# RFID_System_Board.net
KiCad netlist of a schematic drawn in EAGLE
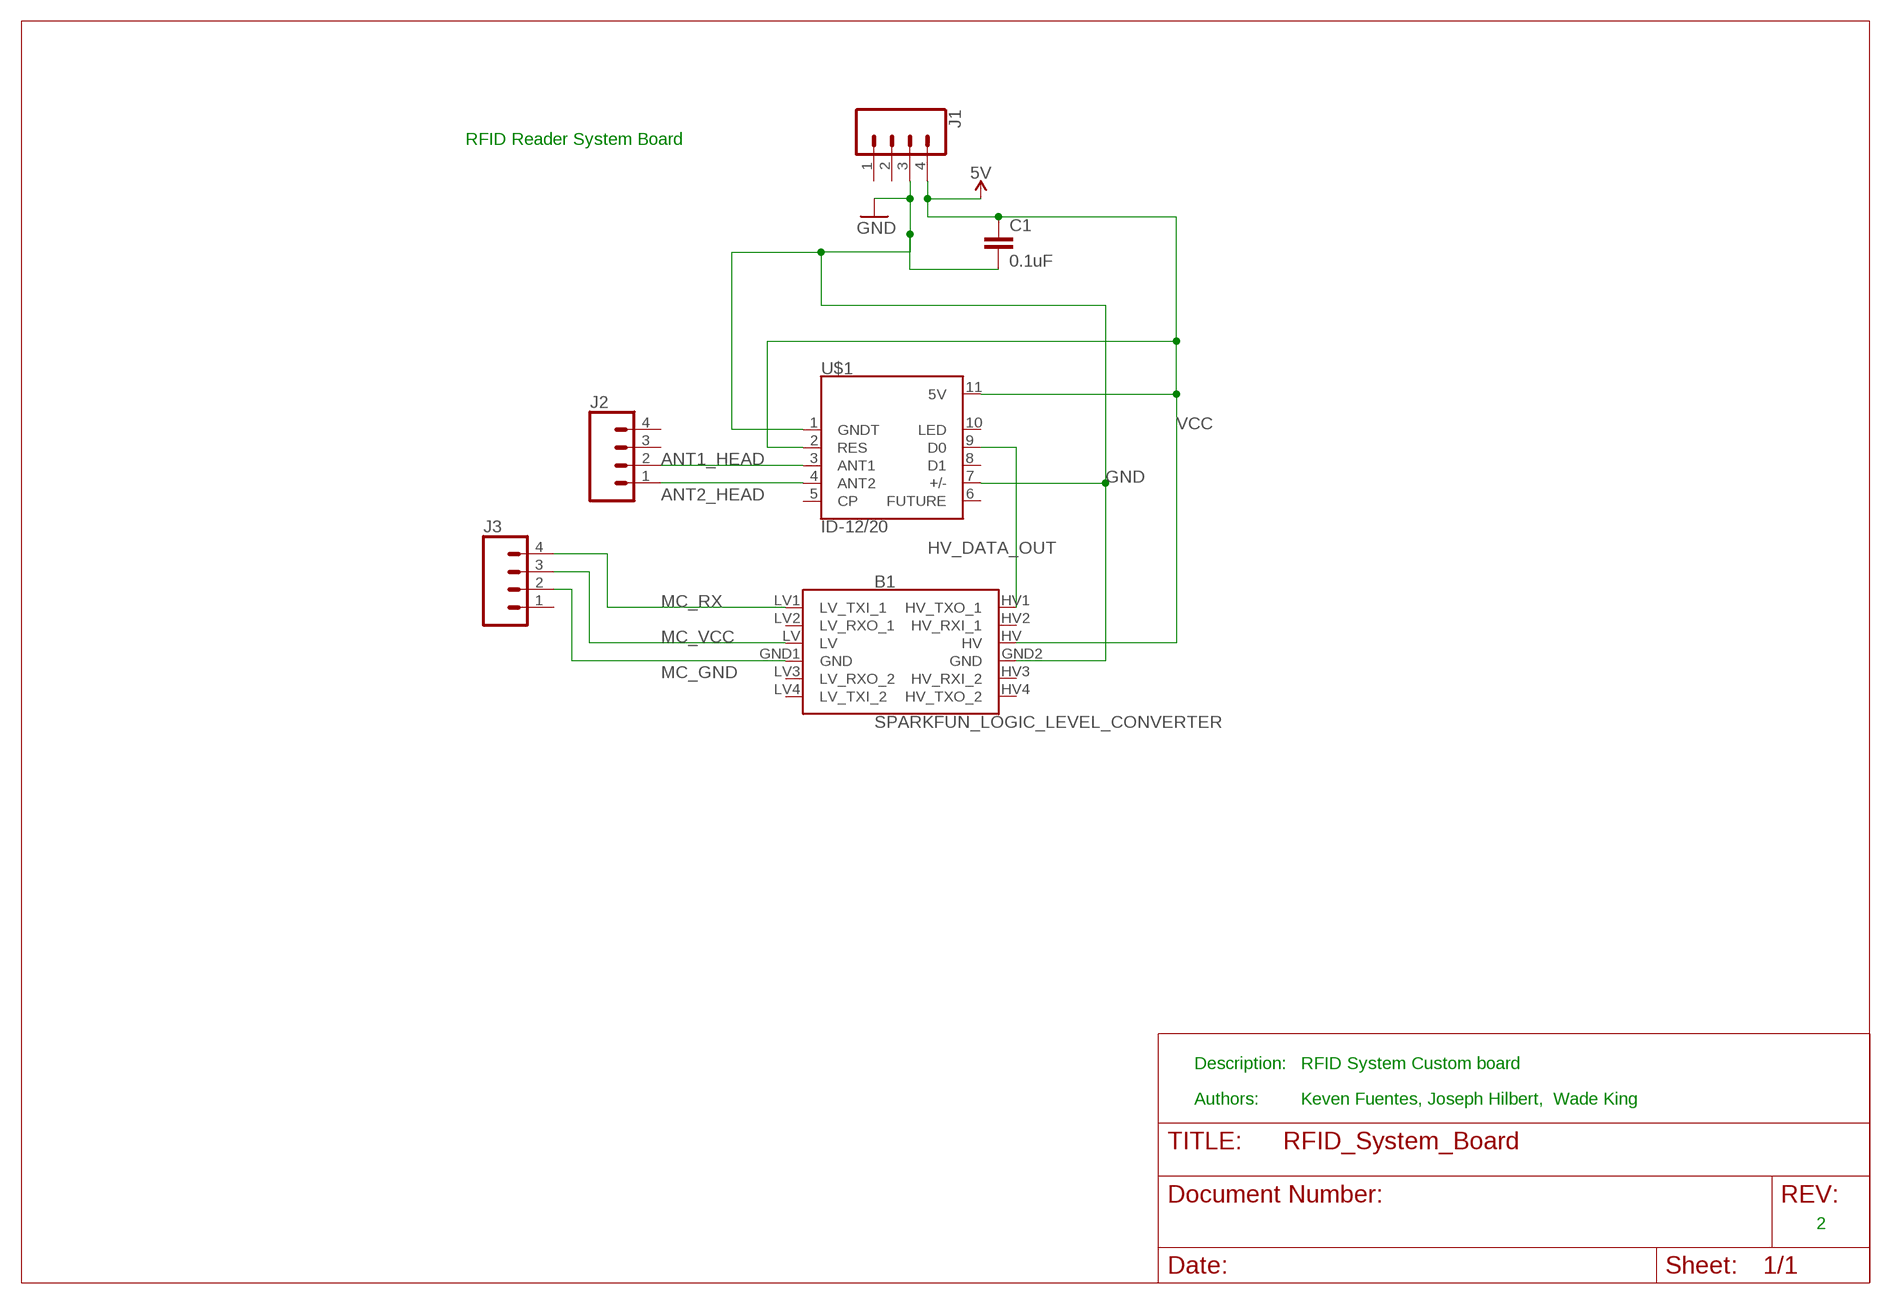
[diagram p0: schematic, sheet 1]

(export (version "E")
  (design (tool "Eeschema 10.0.6"))
  (components
    (comp (ref "B1")
      (value "SPARKFUN_LOGIC_LEVEL_CONVERTER")
      (footprint "eagle-import:SPARKFUN_LOGIC_LEVEL_CONVERTER")
      (libsource (lib "eagle-import") (part "SPARKFUN_LOGIC_LEVEL_CONVERTER"))
    )
    (comp (ref "C1")
      (value "0.1uF")
      (footprint "eagle-import:0603")
      (libsource (lib "eagle-import") (part "0.1UF-0603-25V-(+80/-20%)"))
    )
    (comp (ref "J1")
      (value "CONN_04")
      (footprint "eagle-import:1X04")
      (libsource (lib "eagle-import") (part "CONN_04"))
    )
    (comp (ref "J2")
      (value "CONN_04")
      (footprint "eagle-import:1X04")
      (libsource (lib "eagle-import") (part "CONN_04"))
    )
    (comp (ref "J3")
      (value "CONN_04")
      (footprint "eagle-import:1X04")
      (libsource (lib "eagle-import") (part "CONN_04"))
    )
    (comp (ref "U$1")
      (value "ID-12/20")
      (footprint "eagle-import:ID-12")
      (libsource (lib "eagle-import") (part "ID-12/20"))
    )
  )
  (nets
    (net (code "1") (name "/ANT1_HEAD") (class "Default")
      (node (ref "J2") (pin "2") (pinfunction "2_2") (pintype "passive"))
      (node (ref "U$1") (pin "3") (pinfunction "ANT1_3") (pintype "bidirectional"))
    )
    (net (code "2") (name "/ANT2_HEAD") (class "Default")
      (node (ref "J2") (pin "1") (pinfunction "1_1") (pintype "passive"))
      (node (ref "U$1") (pin "4") (pinfunction "ANT2_4") (pintype "bidirectional"))
    )
    (net (code "3") (name "/HV_DATA_OUT") (class "Default")
      (node (ref "B1") (pin "HV1") (pinfunction "HV_TXO_1_HV1") (pintype "bidirectional"))
      (node (ref "U$1") (pin "9") (pinfunction "D0_9") (pintype "bidirectional"))
    )
    (net (code "4") (name "/MC_GND") (class "Default")
      (node (ref "B1") (pin "GND1") (pinfunction "GND_GND1") (pintype "power_in"))
      (node (ref "J3") (pin "2") (pinfunction "2_2") (pintype "passive"))
    )
    (net (code "5") (name "/MC_RX") (class "Default")
      (node (ref "B1") (pin "LV1") (pinfunction "LV_TXI_1_LV1") (pintype "bidirectional"))
      (node (ref "J3") (pin "4") (pinfunction "4_4") (pintype "passive"))
    )
    (net (code "6") (name "/MC_VCC") (class "Default")
      (node (ref "B1") (pin "LV") (pinfunction "LV_LV") (pintype "power_in"))
      (node (ref "J3") (pin "3") (pinfunction "3_3") (pintype "passive"))
    )
    (net (code "7") (name "5V") (class "Default")
      (node (ref "B1") (pin "HV") (pinfunction "HV_HV") (pintype "power_in"))
      (node (ref "C1") (pin "1") (pinfunction "1_1") (pintype "passive"))
      (node (ref "J1") (pin "4") (pinfunction "4_4") (pintype "passive"))
      (node (ref "U$1") (pin "11") (pinfunction "5V_11") (pintype "bidirectional"))
      (node (ref "U$1") (pin "2") (pinfunction "RES_2") (pintype "bidirectional"))
    )
    (net (code "8") (name "GND") (class "Default")
      (node (ref "B1") (pin "GND2") (pinfunction "GND_GND2") (pintype "power_in"))
      (node (ref "C1") (pin "2") (pinfunction "2_2") (pintype "passive"))
      (node (ref "J1") (pin "3") (pinfunction "3_3") (pintype "passive"))
      (node (ref "U$1") (pin "1") (pinfunction "GNDT_1") (pintype "bidirectional"))
      (node (ref "U$1") (pin "7") (pinfunction "+/-_7") (pintype "bidirectional"))
    )
    (net (code "9") (name "unconnected-(B1-HV_RXI_1-PadHV2)") (class "Default")
      (node (ref "B1") (pin "HV2") (pinfunction "HV_RXI_1_HV2") (pintype "bidirectional"))
    )
    (net (code "10") (name "unconnected-(B1-HV_RXI_2-PadHV3)") (class "Default")
      (node (ref "B1") (pin "HV3") (pinfunction "HV_RXI_2_HV3") (pintype "bidirectional"))
    )
    (net (code "11") (name "unconnected-(B1-HV_TXO_2-PadHV4)") (class "Default")
      (node (ref "B1") (pin "HV4") (pinfunction "HV_TXO_2_HV4") (pintype "bidirectional"))
    )
    (net (code "12") (name "unconnected-(B1-LV_RXO_1-PadLV2)") (class "Default")
      (node (ref "B1") (pin "LV2") (pinfunction "LV_RXO_1_LV2") (pintype "bidirectional"))
    )
    (net (code "13") (name "unconnected-(B1-LV_RXO_2-PadLV3)") (class "Default")
      (node (ref "B1") (pin "LV3") (pinfunction "LV_RXO_2_LV3") (pintype "bidirectional"))
    )
    (net (code "14") (name "unconnected-(B1-LV_TXI_2-PadLV4)") (class "Default")
      (node (ref "B1") (pin "LV4") (pinfunction "LV_TXI_2_LV4") (pintype "bidirectional"))
    )
    (net (code "15") (name "unconnected-(J1-Pad1)") (class "Default")
      (node (ref "J1") (pin "1") (pinfunction "1_1") (pintype "passive"))
    )
    (net (code "16") (name "unconnected-(J1-Pad2)") (class "Default")
      (node (ref "J1") (pin "2") (pinfunction "2_2") (pintype "passive"))
    )
    (net (code "17") (name "unconnected-(J2-Pad3)") (class "Default")
      (node (ref "J2") (pin "3") (pinfunction "3_3") (pintype "passive"))
    )
    (net (code "18") (name "unconnected-(J2-Pad4)") (class "Default")
      (node (ref "J2") (pin "4") (pinfunction "4_4") (pintype "passive"))
    )
    (net (code "19") (name "unconnected-(J3-Pad1)") (class "Default")
      (node (ref "J3") (pin "1") (pinfunction "1_1") (pintype "passive"))
    )
    (net (code "20") (name "unconnected-(U$1-CP-Pad5)") (class "Default")
      (node (ref "U$1") (pin "5") (pinfunction "CP_5") (pintype "bidirectional"))
    )
    (net (code "21") (name "unconnected-(U$1-D1-Pad8)") (class "Default")
      (node (ref "U$1") (pin "8") (pinfunction "D1_8") (pintype "bidirectional"))
    )
    (net (code "22") (name "unconnected-(U$1-FUTURE-Pad6)") (class "Default")
      (node (ref "U$1") (pin "6") (pinfunction "FUTURE_6") (pintype "bidirectional"))
    )
    (net (code "23") (name "unconnected-(U$1-LED-Pad10)") (class "Default")
      (node (ref "U$1") (pin "10") (pinfunction "LED_10") (pintype "bidirectional"))
    )
  )
)
